# Fluxus.net
KiCad netlist of a schematic drawn in Altium Designer
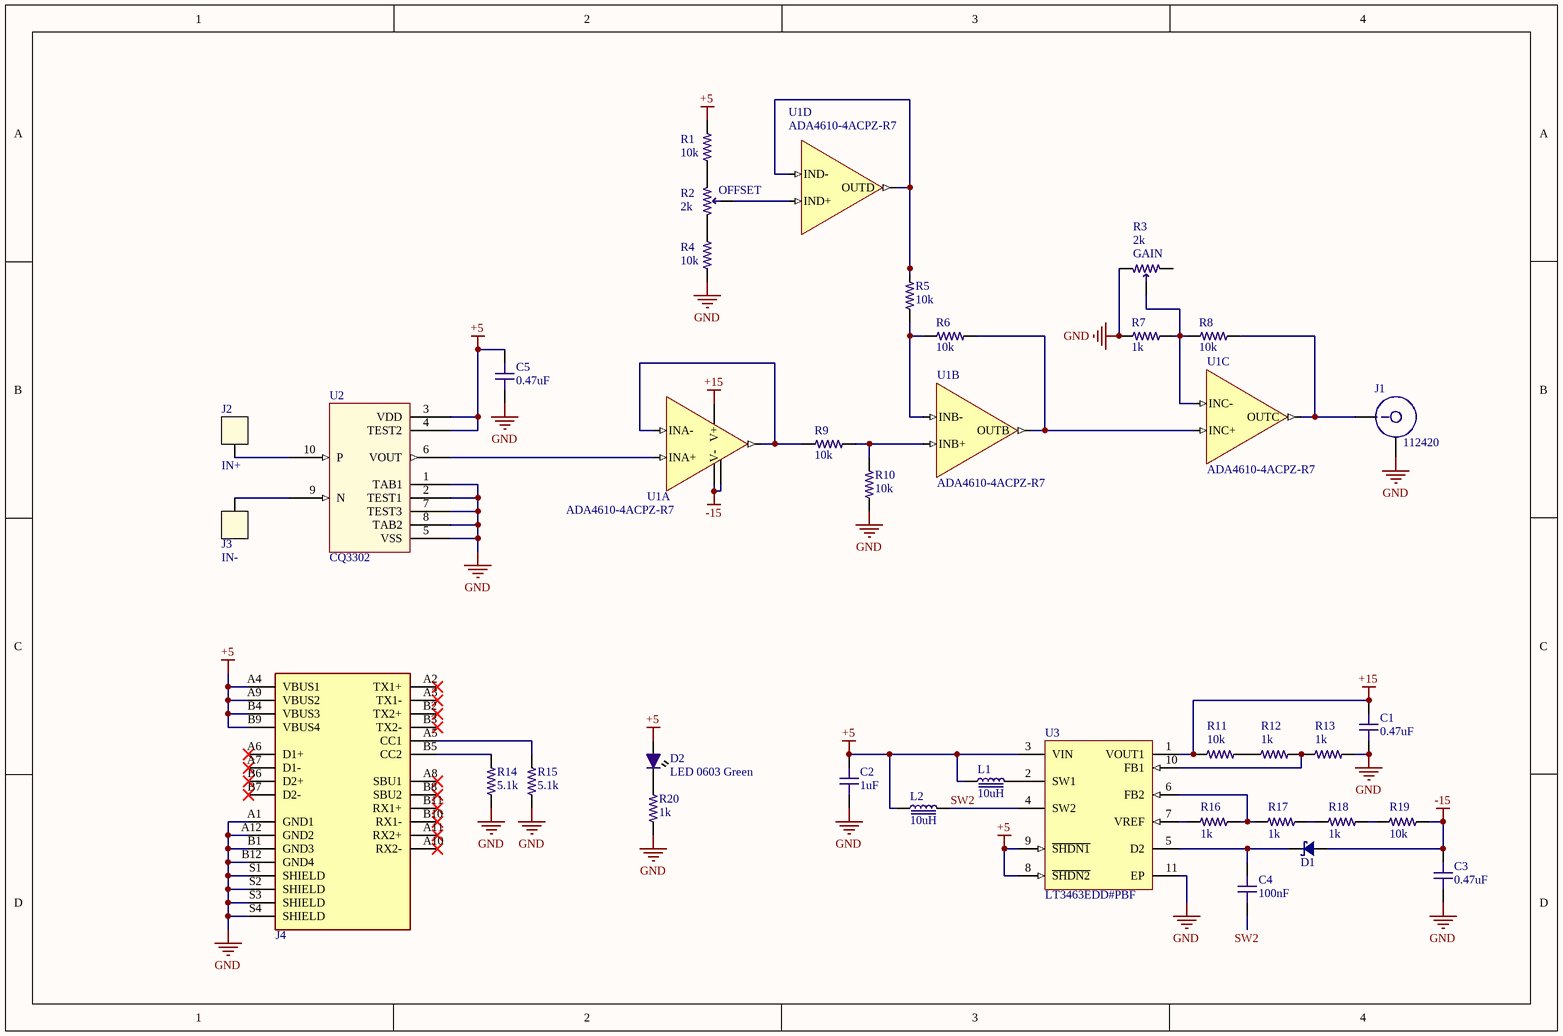
[diagram p0: Fluxus.SchDoc]

(export (version "E")
  (design (tool "Eeschema 10.0.6"))
  (components
    (comp (ref "C1")
      (value "0.47uF")
      (footprint "C0603-HIGH-DENSITY")
      (description "Chip Capacitor, 0603, 0.47uF, 50V, X7R")
      (fields (field (name "Comment") "C0603 0.47uF 50V X7R"))
      (libsource (lib "Capacitors") (part "C0603 0.47uF 50V X7R"))
    )
    (comp (ref "C2")
      (value "1uF")
      (footprint "C0603-HIGH-DENSITY")
      (description "CAP CER 1UF 25V X7R 0603")
      (fields (field (name "Comment") "C0603 1uF 25V X7R"))
      (libsource (lib "Capacitors") (part "C0603 1uF 25V X7R"))
    )
    (comp (ref "C3")
      (value "0.47uF")
      (footprint "C0603-HIGH-DENSITY")
      (description "Chip Capacitor, 0603, 0.47uF, 50V, X7R")
      (fields (field (name "Comment") "C0603 0.47uF 50V X7R"))
      (libsource (lib "Capacitors") (part "C0603 0.47uF 50V X7R"))
    )
    (comp (ref "C4")
      (value "100nF")
      (footprint "C0603-HIGH-DENSITY")
      (description "CAP CER 0.1UF 50V X7R 0603")
      (fields (field (name "Comment") "C0603 100nF 50V X7R"))
      (libsource (lib "Capacitors") (part "C0603 100nF 50V X7R"))
    )
    (comp (ref "C5")
      (value "0.47uF")
      (footprint "C0603-HIGH-DENSITY")
      (description "Chip Capacitor, 0603, 0.47uF, 50V, X7R")
      (fields (field (name "Comment") "C0603 0.47uF 50V X7R"))
      (libsource (lib "Capacitors") (part "C0603 0.47uF 50V X7R"))
    )
    (comp (ref "D1")
      (value "B0540WQ-7-F")
      (footprint "SOD123W")
      (description "DIODE SCHOTTKY 40V 500MA SOD123")
      (libsource (lib "Diodes") (part "B0540WQ-7-F"))
    )
    (comp (ref "D2")
      (value "LED 0603 Green")
      (footprint "LED0603-IPC")
      (description "LED GREEN CLEAR 0603 SMD")
      (libsource (lib "Diodes") (part "LED 0603 Green"))
    )
    (comp (ref "J1")
      (value "112420")
      (footprint "BNC_Plug, Male Pin Panel Mount")
      (description "BNC Connector Plug, Male Pin 50Ohm Panel Mount Solder Cup")
      (libsource (lib "RF Components") (part "BNC"))
    )
    (comp (ref "J2")
      (value "IN+")
      (footprint "Banana Jack")
      (description "JACK NON-INSULATED .350\"")
      (libsource (lib "Connectors") (part "Banana Jack"))
    )
    (comp (ref "J3")
      (value "IN-")
      (footprint "Banana Jack")
      (description "JACK NON-INSULATED .350\"")
      (libsource (lib "") (part "Banana Jack_1"))
    )
    (comp (ref "J4")
      (value "USB C")
      (footprint "Molex USB-C")
      (fields
        (field (name "MF") "Molex")
        (field (name "DIGI-KEY_PART_NUMBER") "WM12856CT-ND")
        (field (name "MP") "1054500101")
      )
      (libsource (lib "Connectors") (part "USB C"))
    )
    (comp (ref "L1")
      (value "10uH")
      (footprint "LQH32C L1210")
      (description "FIXED IND 10UH 450MA 390 MOHM, UNSHIELDED WIREWOUND")
      (fields (field (name "Comment") "LQH32CN100K33L"))
      (libsource (lib "Inductors") (part "LQH32CN100K33L"))
    )
    (comp (ref "L2")
      (value "10uH")
      (footprint "LQH32C L1210")
      (description "FIXED IND 10UH 450MA 390 MOHM, UNSHIELDED WIREWOUND")
      (fields (field (name "Comment") "LQH32CN100K33L"))
      (libsource (lib "Inductors") (part "LQH32CN100K33L"))
    )
    (comp (ref "R1")
      (value "10k")
      (footprint "R0402-IPC")
      (description "Chip Resistor, 0402, 10k ohms, 1%, 1/16 W")
      (fields (field (name "Comment") "R0402 10k 1%"))
      (libsource (lib "Resistors") (part "R0402 10k 1%"))
    )
    (comp (ref "R2")
      (value "OFFSET")
      (footprint "POT3.25-2")
      (description "Surface Mount Trimmer")
      (fields (field (name "ALTIUM_VALUE") "2k"))
      (libsource (lib "Resistors") (part "RPot"))
    )
    (comp (ref "R3")
      (value "GAIN")
      (footprint "POT3.25-2")
      (description "Surface Mount Trimmer")
      (fields (field (name "ALTIUM_VALUE") "2k"))
      (libsource (lib "Resistors") (part "RPot"))
    )
    (comp (ref "R4")
      (value "10k")
      (footprint "R0402-IPC")
      (description "Chip Resistor, 0402, 10k ohms, 1%, 1/16 W")
      (fields (field (name "Comment") "R0402 10k 1%"))
      (libsource (lib "Resistors") (part "R0402 10k 1%"))
    )
    (comp (ref "R5")
      (value "10k")
      (footprint "R0402-IPC")
      (description "Chip Resistor, 0402, 10k ohms, 1%, 1/16 W")
      (fields (field (name "Comment") "R0402 10k 1%"))
      (libsource (lib "Resistors") (part "R0402 10k 1%"))
    )
    (comp (ref "R6")
      (value "10k")
      (footprint "R0402-IPC")
      (description "Chip Resistor, 0402, 10k ohms, 1%, 1/16 W")
      (fields (field (name "Comment") "R0402 10k 1%"))
      (libsource (lib "Resistors") (part "R0402 10k 1%"))
    )
    (comp (ref "R7")
      (value "1k")
      (footprint "R0402-IPC")
      (description "Chip Resistor, 0402, 1k ohms, 1%, 1/16 W")
      (fields (field (name "Comment") "R0402 1k 1%"))
      (libsource (lib "Resistors") (part "R0402 1k 1%"))
    )
    (comp (ref "R8")
      (value "10k")
      (footprint "R0402-IPC")
      (description "Chip Resistor, 0402, 10k ohms, 1%, 1/16 W")
      (fields (field (name "Comment") "R0402 10k 1%"))
      (libsource (lib "Resistors") (part "R0402 10k 1%"))
    )
    (comp (ref "R9")
      (value "10k")
      (footprint "R0402-IPC")
      (description "Chip Resistor, 0402, 10k ohms, 1%, 1/16 W")
      (fields (field (name "Comment") "R0402 10k 1%"))
      (libsource (lib "Resistors") (part "R0402 10k 1%"))
    )
    (comp (ref "R10")
      (value "10k")
      (footprint "R0402-IPC")
      (description "Chip Resistor, 0402, 10k ohms, 1%, 1/16 W")
      (fields (field (name "Comment") "R0402 10k 1%"))
      (libsource (lib "Resistors") (part "R0402 10k 1%"))
    )
    (comp (ref "R11")
      (value "10k")
      (footprint "R0402-IPC")
      (description "Chip Resistor, 0402, 10k ohms, 1%, 1/16 W")
      (fields (field (name "Comment") "R0402 10k 1%"))
      (libsource (lib "Resistors") (part "R0402 10k 1%"))
    )
    (comp (ref "R12")
      (value "1k")
      (footprint "R0402-IPC")
      (description "Chip Resistor, 0402, 1k ohms, 1%, 1/16 W")
      (fields (field (name "Comment") "R0402 1k 1%"))
      (libsource (lib "Resistors") (part "R0402 1k 1%"))
    )
    (comp (ref "R13")
      (value "1k")
      (footprint "R0402-IPC")
      (description "Chip Resistor, 0402, 1k ohms, 1%, 1/16 W")
      (fields (field (name "Comment") "R0402 1k 1%"))
      (libsource (lib "Resistors") (part "R0402 1k 1%"))
    )
    (comp (ref "R14")
      (value "5.1k")
      (footprint "R0603-HIGH-DENSITY")
      (description "RES SMD 5.1K OHM 1% 1/10W 0603")
      (fields (field (name "Comment") "R0603 5.1K 1%"))
      (libsource (lib "Resistors") (part "R0603 5.1K 1%"))
    )
    (comp (ref "R15")
      (value "5.1k")
      (footprint "R0603-HIGH-DENSITY")
      (description "RES SMD 5.1K OHM 1% 1/10W 0603")
      (fields (field (name "Comment") "R0603 5.1K 1%"))
      (libsource (lib "Resistors") (part "R0603 5.1K 1%"))
    )
    (comp (ref "R16")
      (value "1k")
      (footprint "R0402-IPC")
      (description "Chip Resistor, 0402, 1k ohms, 1%, 1/16 W")
      (fields (field (name "Comment") "R0402 1k 1%"))
      (libsource (lib "Resistors") (part "R0402 1k 1%"))
    )
    (comp (ref "R17")
      (value "1k")
      (footprint "R0402-IPC")
      (description "Chip Resistor, 0402, 1k ohms, 1%, 1/16 W")
      (fields (field (name "Comment") "R0402 1k 1%"))
      (libsource (lib "Resistors") (part "R0402 1k 1%"))
    )
    (comp (ref "R18")
      (value "1k")
      (footprint "R0402-IPC")
      (description "Chip Resistor, 0402, 1k ohms, 1%, 1/16 W")
      (fields (field (name "Comment") "R0402 1k 1%"))
      (libsource (lib "Resistors") (part "R0402 1k 1%"))
    )
    (comp (ref "R19")
      (value "10k")
      (footprint "R0402-IPC")
      (description "Chip Resistor, 0402, 10k ohms, 1%, 1/16 W")
      (fields (field (name "Comment") "R0402 10k 1%"))
      (libsource (lib "Resistors") (part "R0402 10k 1%"))
    )
    (comp (ref "R20")
      (value "1k")
      (footprint "R0402-IPC")
      (description "Chip Resistor, 0402, 1k ohms, 1%, 1/16 W")
      (fields (field (name "Comment") "R0402 1k 1%"))
      (libsource (lib "Resistors") (part "R0402 1k 1%"))
    )
    (comp (ref "U1")
      (value "ADA4610-4ACPZ-R7")
      (footprint "LFCSP16 4x4x0.75mm")
      (description "IC OPAMP JFET 4 CIRCUIT 16LFCSP")
      (libsource (lib "Integrated Circuits") (part "ADA4610-4ACPZ-R7"))
    )
    (comp (ref "U2")
      (value "CQ3302")
      (footprint "24-LSSOP CQ3302 Specific")
      (libsource (lib "Integrated Circuits") (part "CQ3302"))
    )
    (comp (ref "U3")
      (value "LT3463EDD#PBF")
      (footprint "DFN-10")
      (fields
        (field (name "MANUFACTURER") "Linear Technology")
        (field (name "MANUFACTURER_1") "Analog Devices / Linear Technology")
      )
      (libsource (lib "Integrated Circuits") (part "LT3463EDD"))
    )
  )
  (nets
    (net (code "1") (name "+5") (class "Default")
      (node (ref "C2") (pin "2") (pintype "passive"))
      (node (ref "C5") (pin "2") (pintype "passive"))
      (node (ref "D2") (pin "A") (pintype "passive"))
      (node (ref "J4") (pin "A4") (pinfunction "VBUS1_A4") (pintype "passive"))
      (node (ref "J4") (pin "A9") (pinfunction "VBUS2_A9") (pintype "passive"))
      (node (ref "J4") (pin "B4") (pinfunction "VBUS3_B4") (pintype "passive"))
      (node (ref "J4") (pin "B9") (pinfunction "VBUS4_B9") (pintype "passive"))
      (node (ref "L1") (pin "1") (pintype "passive"))
      (node (ref "L2") (pin "1") (pintype "passive"))
      (node (ref "R1") (pin "2") (pintype "passive"))
      (node (ref "U2") (pin "3") (pinfunction "VDD_3") (pintype "power_in"))
      (node (ref "U2") (pin "4") (pinfunction "TEST2_4") (pintype "power_in"))
      (node (ref "U3") (pin "3") (pinfunction "VIN_3") (pintype "power_in"))
      (node (ref "U3") (pin "8") (pinfunction "~{SHDN2}_8") (pintype "input"))
      (node (ref "U3") (pin "9") (pinfunction "~{SHDN1}_9") (pintype "input"))
    )
    (net (code "2") (name "+15") (class "Default")
      (node (ref "C1") (pin "2") (pintype "passive"))
      (node (ref "R11") (pin "2") (pintype "passive"))
      (node (ref "U1") (pin "3") (pinfunction "V+_3") (pintype "power_in"))
      (node (ref "U3") (pin "1") (pinfunction "VOUT1_1") (pintype "power_in"))
    )
    (net (code "3") (name "-15") (class "Default")
      (node (ref "C3") (pin "2") (pintype "passive"))
      (node (ref "D1") (pin "2") (pinfunction "2_2") (pintype "passive"))
      (node (ref "R19") (pin "2") (pintype "passive"))
      (node (ref "U1") (pin "10") (pinfunction "V-_10") (pintype "power_in"))
      (node (ref "U1") (pin "17") (pinfunction "PAD_17") (pintype "power_in"))
    )
    (net (code "4") (name "/SW2") (class "Default")
      (node (ref "C4") (pin "1") (pintype "passive"))
      (node (ref "L2") (pin "2") (pintype "passive"))
      (node (ref "U3") (pin "4") (pinfunction "SW2_4") (pintype "power_in"))
    )
    (net (code "5") (name "GND") (class "Default")
      (node (ref "C1") (pin "1") (pintype "passive"))
      (node (ref "C2") (pin "1") (pintype "passive"))
      (node (ref "C3") (pin "1") (pintype "passive"))
      (node (ref "C5") (pin "1") (pintype "passive"))
      (node (ref "J1") (pin "G") (pintype "passive"))
      (node (ref "J4") (pin "A1") (pinfunction "GND1_A1") (pintype "passive"))
      (node (ref "J4") (pin "A12") (pinfunction "GND2_A12") (pintype "passive"))
      (node (ref "J4") (pin "B1") (pinfunction "GND3_B1") (pintype "passive"))
      (node (ref "J4") (pin "B12") (pinfunction "GND4_B12") (pintype "passive"))
      (node (ref "J4") (pin "S1") (pinfunction "SHIELD_S1") (pintype "passive"))
      (node (ref "J4") (pin "S2") (pinfunction "SHIELD_S2") (pintype "passive"))
      (node (ref "J4") (pin "S3") (pinfunction "SHIELD_S3") (pintype "passive"))
      (node (ref "J4") (pin "S4") (pinfunction "SHIELD_S4") (pintype "passive"))
      (node (ref "R10") (pin "2") (pintype "passive"))
      (node (ref "R13") (pin "1") (pintype "passive"))
      (node (ref "R14") (pin "1") (pintype "passive"))
      (node (ref "R15") (pin "1") (pintype "passive"))
      (node (ref "R20") (pin "1") (pintype "passive"))
      (node (ref "R3") (pin "3") (pintype "passive"))
      (node (ref "R4") (pin "1") (pintype "passive"))
      (node (ref "R7") (pin "1") (pintype "passive"))
      (node (ref "U2") (pin "1") (pinfunction "TAB1_1") (pintype "power_in"))
      (node (ref "U2") (pin "2") (pinfunction "TEST1_2") (pintype "power_in"))
      (node (ref "U2") (pin "5") (pinfunction "VSS_5") (pintype "power_in"))
      (node (ref "U2") (pin "7") (pinfunction "TEST3_7") (pintype "power_in"))
      (node (ref "U2") (pin "8") (pinfunction "TAB2_8") (pintype "power_in"))
      (node (ref "U3") (pin "11") (pinfunction "EP_11") (pintype "power_in"))
    )
    (net (code "6") (name "Net-(D2-PadK)") (class "Default")
      (node (ref "D2") (pin "K") (pintype "passive"))
      (node (ref "R20") (pin "2") (pintype "passive"))
    )
    (net (code "7") (name "Net-(J4-CC1)") (class "Default")
      (node (ref "J4") (pin "A5") (pinfunction "CC1_A5") (pintype "passive"))
      (node (ref "R15") (pin "2") (pintype "passive"))
    )
    (net (code "8") (name "Net-(J4-CC2)") (class "Default")
      (node (ref "J4") (pin "B5") (pinfunction "CC2_B5") (pintype "passive"))
      (node (ref "R14") (pin "2") (pintype "passive"))
    )
    (net (code "9") (name "Net-(R1-Pad1)") (class "Default")
      (node (ref "R1") (pin "1") (pintype "passive"))
      (node (ref "R2") (pin "1") (pintype "passive"))
    )
    (net (code "10") (name "Net-(R2-Pad3)") (class "Default")
      (node (ref "R2") (pin "3") (pintype "passive"))
      (node (ref "R4") (pin "2") (pintype "passive"))
    )
    (net (code "11") (name "Net-(R2-W)") (class "Default")
      (node (ref "R2") (pin "2") (pinfunction "W_2") (pintype "passive"))
      (node (ref "U1") (pin "11") (pinfunction "IND+_11") (pintype "input"))
    )
    (net (code "12") (name "Net-(R3-W)") (class "Default")
      (node (ref "R3") (pin "2") (pinfunction "W_2") (pintype "passive"))
      (node (ref "R7") (pin "2") (pintype "passive"))
      (node (ref "R8") (pin "1") (pintype "passive"))
      (node (ref "U1") (pin "8") (pinfunction "INC-_8") (pintype "input"))
    )
    (net (code "13") (name "Net-(R11-Pad1)") (class "Default")
      (node (ref "R11") (pin "1") (pintype "passive"))
      (node (ref "R12") (pin "2") (pintype "passive"))
    )
    (net (code "14") (name "Net-(R17-Pad1)") (class "Default")
      (node (ref "R17") (pin "1") (pintype "passive"))
      (node (ref "R18") (pin "2") (pintype "passive"))
    )
    (net (code "15") (name "Net-(R18-Pad1)") (class "Default")
      (node (ref "R18") (pin "1") (pintype "passive"))
      (node (ref "R19") (pin "1") (pintype "passive"))
    )
    (net (code "16") (name "Net-(U1A-INA+)") (class "Default")
      (node (ref "U1") (pin "2") (pinfunction "INA+_2") (pintype "input"))
      (node (ref "U2") (pin "6") (pinfunction "VOUT_6") (pintype "output"))
    )
    (net (code "17") (name "Net-(U1A-INA-)") (class "Default")
      (node (ref "R9") (pin "1") (pintype "passive"))
      (node (ref "U1") (pin "1") (pinfunction "INA-_1") (pintype "input"))
      (node (ref "U1") (pin "15") (pinfunction "OUTA_15") (pintype "output"))
    )
    (net (code "18") (name "Net-(U1B-INB+)") (class "Default")
      (node (ref "R10") (pin "1") (pintype "passive"))
      (node (ref "R9") (pin "2") (pintype "passive"))
      (node (ref "U1") (pin "4") (pinfunction "INB+_4") (pintype "input"))
    )
    (net (code "19") (name "Net-(U1B-INB-)") (class "Default")
      (node (ref "R5") (pin "2") (pintype "passive"))
      (node (ref "R6") (pin "2") (pintype "passive"))
      (node (ref "U1") (pin "5") (pinfunction "INB-_5") (pintype "input"))
    )
    (net (code "20") (name "Net-(U1B-OUTB)") (class "Default")
      (node (ref "R6") (pin "1") (pintype "passive"))
      (node (ref "U1") (pin "6") (pinfunction "OUTB_6") (pintype "output"))
      (node (ref "U1") (pin "9") (pinfunction "INC+_9") (pintype "input"))
    )
    (net (code "21") (name "Net-(U1C-OUTC)") (class "Default")
      (node (ref "J1") (pin "C") (pintype "passive"))
      (node (ref "R8") (pin "2") (pintype "passive"))
      (node (ref "U1") (pin "7") (pinfunction "OUTC_7") (pintype "output"))
    )
    (net (code "22") (name "Net-(U1D-IND-)") (class "Default")
      (node (ref "R5") (pin "1") (pintype "passive"))
      (node (ref "U1") (pin "12") (pinfunction "IND-_12") (pintype "input"))
      (node (ref "U1") (pin "14") (pinfunction "OUTD_14") (pintype "output"))
    )
    (net (code "23") (name "Net-(U2-N)") (class "Default")
      (node (ref "J3") (pin "1") (pinfunction "1_1") (pintype "passive"))
      (node (ref "U2") (pin "9") (pinfunction "N_9") (pintype "input"))
    )
    (net (code "24") (name "Net-(U2-P)") (class "Default")
      (node (ref "J2") (pin "1") (pinfunction "1_1") (pintype "passive"))
      (node (ref "U2") (pin "10") (pinfunction "P_10") (pintype "input"))
    )
    (net (code "25") (name "Net-(U3-D2)") (class "Default")
      (node (ref "C4") (pin "2") (pintype "passive"))
      (node (ref "D1") (pin "1") (pinfunction "1_1") (pintype "passive"))
      (node (ref "U3") (pin "5") (pinfunction "D2_5") (pintype "passive"))
    )
    (net (code "26") (name "Net-(U3-FB1)") (class "Default")
      (node (ref "R12") (pin "1") (pintype "passive"))
      (node (ref "R13") (pin "2") (pintype "passive"))
      (node (ref "U3") (pin "10") (pinfunction "FB1_10") (pintype "input"))
    )
    (net (code "27") (name "Net-(U3-FB2)") (class "Default")
      (node (ref "R16") (pin "1") (pintype "passive"))
      (node (ref "R17") (pin "2") (pintype "passive"))
      (node (ref "U3") (pin "6") (pinfunction "FB2_6") (pintype "input"))
    )
    (net (code "28") (name "Net-(U3-SW1)") (class "Default")
      (node (ref "L1") (pin "2") (pintype "passive"))
      (node (ref "U3") (pin "2") (pinfunction "SW1_2") (pintype "passive"))
    )
    (net (code "29") (name "Net-(U3-VREF)") (class "Default")
      (node (ref "R16") (pin "2") (pintype "passive"))
      (node (ref "U3") (pin "7") (pinfunction "VREF_7") (pintype "input"))
    )
    (net (code "30") (name "unconnected-(J4-D1+-PadA6)") (class "Default")
      (node (ref "J4") (pin "A6") (pinfunction "D1+_A6") (pintype "passive+no_connect"))
    )
    (net (code "31") (name "unconnected-(J4-D1--PadA7)") (class "Default")
      (node (ref "J4") (pin "A7") (pinfunction "D1-_A7") (pintype "passive+no_connect"))
    )
    (net (code "32") (name "unconnected-(J4-D2+-PadB6)") (class "Default")
      (node (ref "J4") (pin "B6") (pinfunction "D2+_B6") (pintype "passive+no_connect"))
    )
    (net (code "33") (name "unconnected-(J4-D2--PadB7)") (class "Default")
      (node (ref "J4") (pin "B7") (pinfunction "D2-_B7") (pintype "passive+no_connect"))
    )
    (net (code "34") (name "unconnected-(J4-RX1+-PadB11)") (class "Default")
      (node (ref "J4") (pin "B11") (pinfunction "RX1+_B11") (pintype "passive+no_connect"))
    )
    (net (code "35") (name "unconnected-(J4-RX1--PadB10)") (class "Default")
      (node (ref "J4") (pin "B10") (pinfunction "RX1-_B10") (pintype "passive+no_connect"))
    )
    (net (code "36") (name "unconnected-(J4-RX2+-PadA11)") (class "Default")
      (node (ref "J4") (pin "A11") (pinfunction "RX2+_A11") (pintype "passive+no_connect"))
    )
    (net (code "37") (name "unconnected-(J4-RX2--PadA10)") (class "Default")
      (node (ref "J4") (pin "A10") (pinfunction "RX2-_A10") (pintype "passive+no_connect"))
    )
    (net (code "38") (name "unconnected-(J4-SBU1-PadA8)") (class "Default")
      (node (ref "J4") (pin "A8") (pinfunction "SBU1_A8") (pintype "passive+no_connect"))
    )
    (net (code "39") (name "unconnected-(J4-SBU2-PadB8)") (class "Default")
      (node (ref "J4") (pin "B8") (pinfunction "SBU2_B8") (pintype "passive+no_connect"))
    )
    (net (code "40") (name "unconnected-(J4-TX1+-PadA2)") (class "Default")
      (node (ref "J4") (pin "A2") (pinfunction "TX1+_A2") (pintype "passive+no_connect"))
    )
    (net (code "41") (name "unconnected-(J4-TX1--PadA3)") (class "Default")
      (node (ref "J4") (pin "A3") (pinfunction "TX1-_A3") (pintype "passive+no_connect"))
    )
    (net (code "42") (name "unconnected-(J4-TX2+-PadB2)") (class "Default")
      (node (ref "J4") (pin "B2") (pinfunction "TX2+_B2") (pintype "passive+no_connect"))
    )
    (net (code "43") (name "unconnected-(J4-TX2--PadB3)") (class "Default")
      (node (ref "J4") (pin "B3") (pinfunction "TX2-_B3") (pintype "passive+no_connect"))
    )
    (net (code "44") (name "unconnected-(R3-Pad1)") (class "Default")
      (node (ref "R3") (pin "1") (pintype "passive"))
    )
  )
)
